# MainBoard.net
KiCad netlist of a schematic drawn in EAGLE
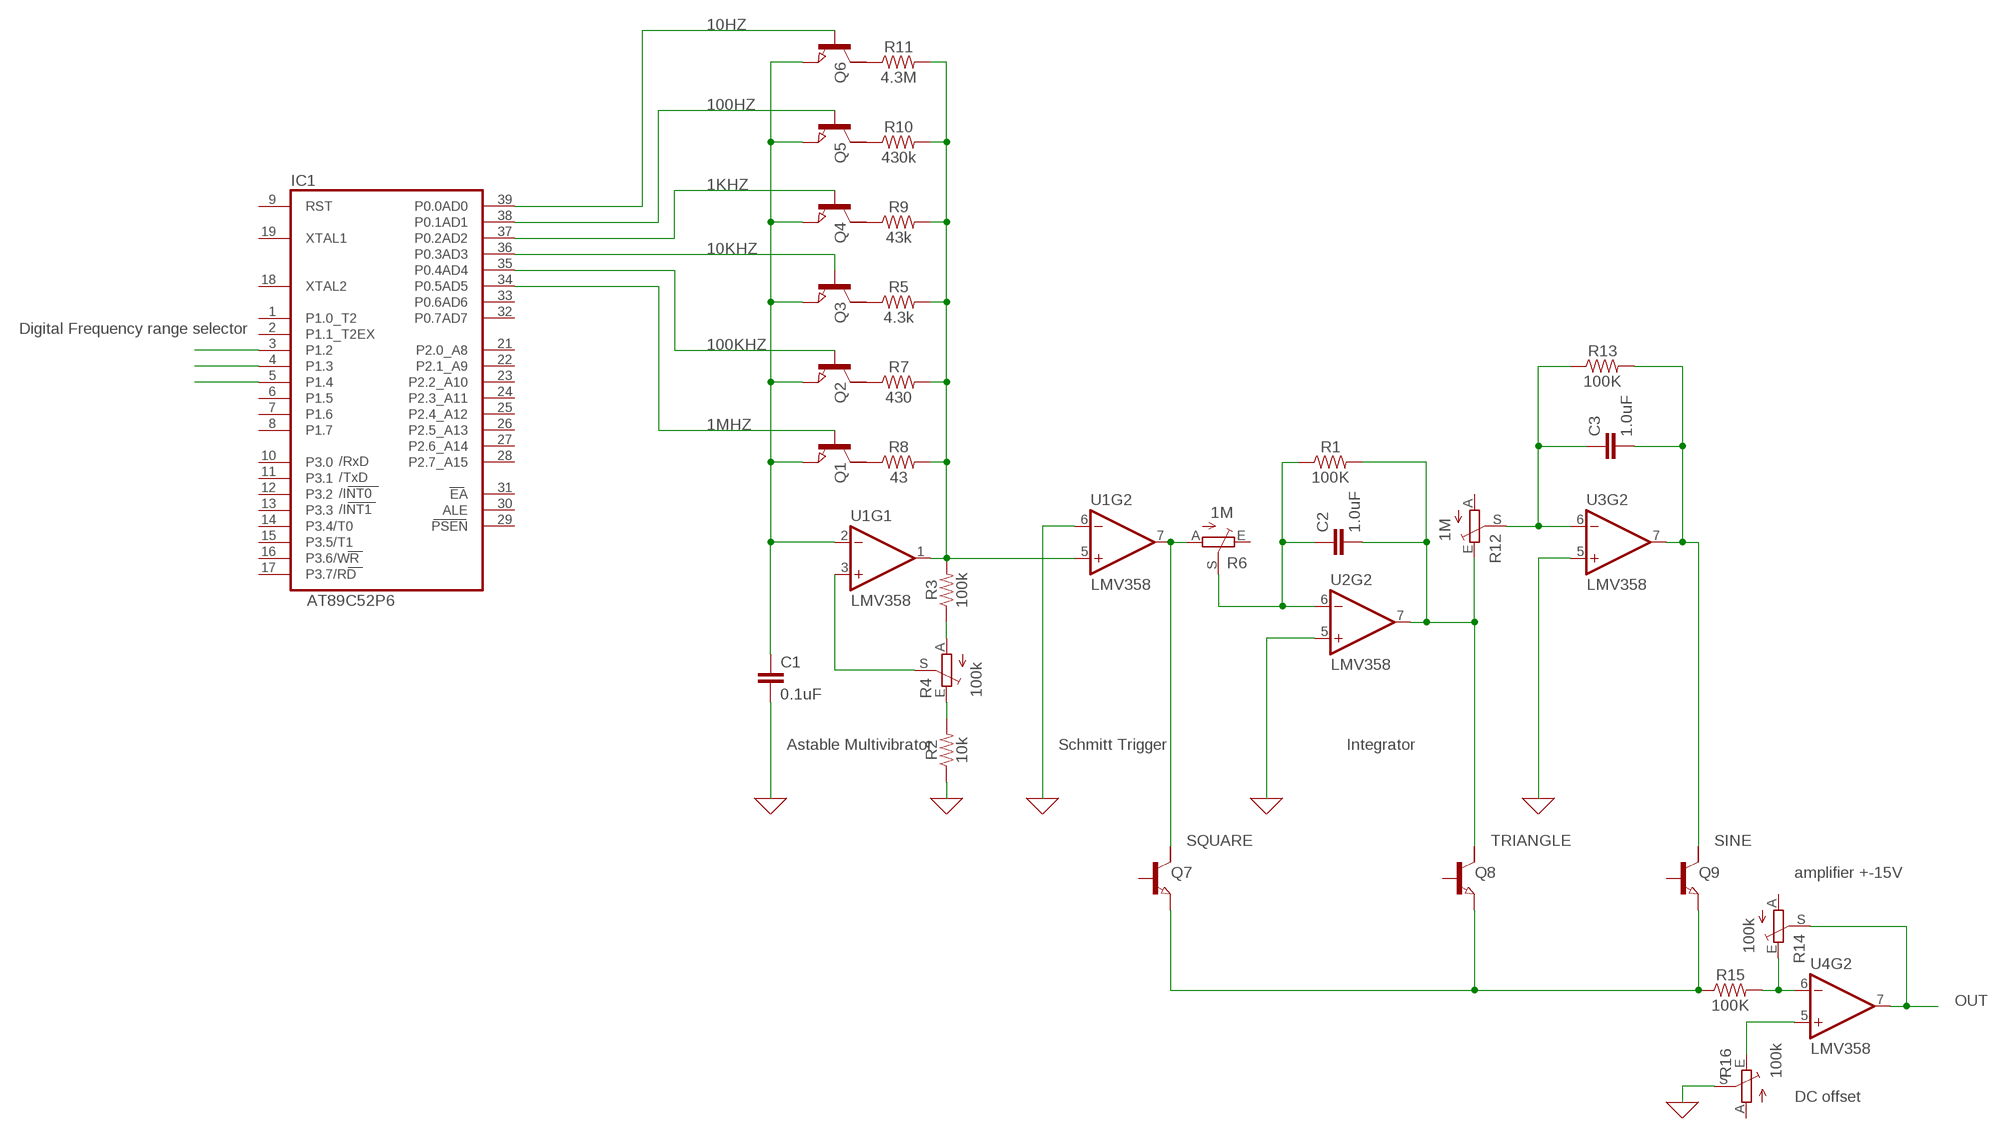
[diagram p0: schematic, sheet 1]

(export (version "E")
  (design (tool "Eeschema 10.0.6"))
  (components
    (comp (ref "C1")
      (value "0.1uF")
      (footprint "eagle-import:0402")
      (libsource (lib "eagle-import") (part "0.1UF-0402-16V-10%"))
    )
    (comp (ref "C2")
      (value "1.0uF")
      (footprint "eagle-import:0402")
      (libsource (lib "eagle-import") (part "1.0UF-0402-16V-10%"))
    )
    (comp (ref "C3")
      (value "1.0uF")
      (footprint "eagle-import:0402")
      (libsource (lib "eagle-import") (part "1.0UF-0402-16V-10%"))
    )
    (comp (ref "IC1")
      (value "AT89C52P6")
      (footprint "eagle-import:DIL40")
      (libsource (lib "eagle-import") (part "AT89C52P6"))
    )
    (comp (ref "Q1")
      (value "NPN-TRANSISTIOR-2COLSOT89")
      (footprint "eagle-import:SOT89")
      (libsource (lib "eagle-import") (part "NPN-TRANSISTIOR-2COLSOT89"))
    )
    (comp (ref "Q2")
      (value "NPN-TRANSISTIOR-2COLSOT89")
      (footprint "eagle-import:SOT89")
      (libsource (lib "eagle-import") (part "NPN-TRANSISTIOR-2COLSOT89"))
    )
    (comp (ref "Q3")
      (value "NPN-TRANSISTIOR-2COLSOT89")
      (footprint "eagle-import:SOT89")
      (libsource (lib "eagle-import") (part "NPN-TRANSISTIOR-2COLSOT89"))
    )
    (comp (ref "Q4")
      (value "NPN-TRANSISTIOR-2COLSOT89")
      (footprint "eagle-import:SOT89")
      (libsource (lib "eagle-import") (part "NPN-TRANSISTIOR-2COLSOT89"))
    )
    (comp (ref "Q5")
      (value "NPN-TRANSISTIOR-2COLSOT89")
      (footprint "eagle-import:SOT89")
      (libsource (lib "eagle-import") (part "NPN-TRANSISTIOR-2COLSOT89"))
    )
    (comp (ref "Q6")
      (value "NPN-TRANSISTIOR-2COLSOT89")
      (footprint "eagle-import:SOT89")
      (libsource (lib "eagle-import") (part "NPN-TRANSISTIOR-2COLSOT89"))
    )
    (comp (ref "Q7")
      (value "NPN-TRANSISTIOR-2COLSOT89")
      (footprint "eagle-import:SOT89")
      (libsource (lib "eagle-import") (part "NPN-TRANSISTIOR-2COLSOT89"))
    )
    (comp (ref "Q8")
      (value "NPN-TRANSISTIOR-2COLSOT89")
      (footprint "eagle-import:SOT89")
      (libsource (lib "eagle-import") (part "NPN-TRANSISTIOR-2COLSOT89"))
    )
    (comp (ref "Q9")
      (value "NPN-TRANSISTIOR-2COLSOT89")
      (footprint "eagle-import:SOT89")
      (libsource (lib "eagle-import") (part "NPN-TRANSISTIOR-2COLSOT89"))
    )
    (comp (ref "R1")
      (value "100K")
      (footprint "eagle-import:0402")
      (libsource (lib "eagle-import") (part "100KOHM-0402-1/16W-1%"))
    )
    (comp (ref "R2")
      (value "10k")
      (footprint "eagle-import:0603")
      (libsource (lib "eagle-import") (part "715OHM-0603-1/10W-1%"))
    )
    (comp (ref "R3")
      (value "100k")
      (footprint "eagle-import:0603")
      (libsource (lib "eagle-import") (part "220KOHM-0603-1/10W-1%"))
    )
    (comp (ref "R4")
      (value "100k")
      (footprint "eagle-import:S64YW")
      (libsource (lib "eagle-import") (part "TRIM_1234-S64YW"))
    )
    (comp (ref "R5")
      (value "4.3k")
      (footprint "eagle-import:0603")
      (libsource (lib "eagle-import") (part "43KOHM-0603-1/10W-1%"))
    )
    (comp (ref "R6")
      (value "1M")
      (footprint "eagle-import:S64YW")
      (libsource (lib "eagle-import") (part "TRIM_1234-S64YW"))
    )
    (comp (ref "R7")
      (value "430")
      (footprint "eagle-import:0603")
      (libsource (lib "eagle-import") (part "43KOHM-0603-1/10W-1%"))
    )
    (comp (ref "R8")
      (value "43")
      (footprint "eagle-import:0603")
      (libsource (lib "eagle-import") (part "43KOHM-0603-1/10W-1%"))
    )
    (comp (ref "R9")
      (value "43k")
      (footprint "eagle-import:0603")
      (libsource (lib "eagle-import") (part "43KOHM-0603-1/10W-1%"))
    )
    (comp (ref "R10")
      (value "430k")
      (footprint "eagle-import:0603")
      (libsource (lib "eagle-import") (part "43KOHM-0603-1/10W-1%"))
    )
    (comp (ref "R11")
      (value "4.3M")
      (footprint "eagle-import:0603")
      (libsource (lib "eagle-import") (part "43KOHM-0603-1/10W-1%"))
    )
    (comp (ref "R12")
      (value "1M")
      (footprint "eagle-import:S64YW")
      (libsource (lib "eagle-import") (part "TRIM_1234-S64YW"))
    )
    (comp (ref "R13")
      (value "100K")
      (footprint "eagle-import:0402")
      (libsource (lib "eagle-import") (part "100KOHM-0402-1/16W-1%"))
    )
    (comp (ref "R14")
      (value "100k")
      (footprint "eagle-import:S64YW")
      (libsource (lib "eagle-import") (part "TRIM_1234-S64YW"))
    )
    (comp (ref "R15")
      (value "100K")
      (footprint "eagle-import:0402")
      (libsource (lib "eagle-import") (part "100KOHM-0402-1/16W-1%"))
    )
    (comp (ref "R16")
      (value "100k")
      (footprint "eagle-import:S64YW")
      (libsource (lib "eagle-import") (part "TRIM_1234-S64YW"))
    )
    (comp (ref "U1")
      (value "LMV358")
      (footprint "eagle-import:SO08")
      (libsource (lib "eagle-import") (part "LMV358SOIC"))
    )
    (comp (ref "U2")
      (value "LMV358")
      (footprint "eagle-import:SO08")
      (libsource (lib "eagle-import") (part "LMV358SOIC"))
    )
    (comp (ref "U3")
      (value "LMV358")
      (footprint "eagle-import:SO08")
      (libsource (lib "eagle-import") (part "LMV358SOIC"))
    )
    (comp (ref "U4")
      (value "LMV358")
      (footprint "eagle-import:SO08")
      (libsource (lib "eagle-import") (part "LMV358SOIC"))
    )
  )
  (nets
    (net (code "1") (name "/1KHZ") (class "Default")
      (node (ref "IC1") (pin "37") (pinfunction "P0.2AD2_37") (pintype "bidirectional"))
      (node (ref "Q4") (pin "1") (pinfunction "B_1") (pintype "passive"))
    )
    (net (code "2") (name "/1MHZ") (class "Default")
      (node (ref "IC1") (pin "34") (pinfunction "P0.5AD5_34") (pintype "bidirectional"))
      (node (ref "Q1") (pin "1") (pinfunction "B_1") (pintype "passive"))
    )
    (net (code "3") (name "/10HZ") (class "Default")
      (node (ref "IC1") (pin "39") (pinfunction "P0.0AD0_39") (pintype "bidirectional"))
      (node (ref "Q6") (pin "1") (pinfunction "B_1") (pintype "passive"))
    )
    (net (code "4") (name "/10KHZ") (class "Default")
      (node (ref "IC1") (pin "36") (pinfunction "P0.3AD3_36") (pintype "bidirectional"))
      (node (ref "Q3") (pin "1") (pinfunction "B_1") (pintype "passive"))
    )
    (net (code "5") (name "/100HZ") (class "Default")
      (node (ref "IC1") (pin "38") (pinfunction "P0.1AD1_38") (pintype "bidirectional"))
      (node (ref "Q5") (pin "1") (pinfunction "B_1") (pintype "passive"))
    )
    (net (code "6") (name "/100KHZ") (class "Default")
      (node (ref "IC1") (pin "35") (pinfunction "P0.4AD4_35") (pintype "bidirectional"))
      (node (ref "Q2") (pin "1") (pinfunction "B_1") (pintype "passive"))
    )
    (net (code "7") (name "/OUT") (class "Default")
      (node (ref "R14") (pin "S") (pinfunction "S_S") (pintype "passive"))
      (node (ref "U4") (pin "7") (pinfunction "OUT_7") (pintype "output"))
    )
    (net (code "8") (name "/SINE") (class "Default")
      (node (ref "C3") (pin "2") (pinfunction "2_2") (pintype "passive"))
      (node (ref "Q9") (pin "2") (pinfunction "C_2") (pintype "passive"))
      (node (ref "R13") (pin "2") (pinfunction "2_2") (pintype "passive"))
      (node (ref "U3") (pin "7") (pinfunction "OUT_7") (pintype "output"))
    )
    (net (code "9") (name "/SQUARE") (class "Default")
      (node (ref "Q7") (pin "2") (pinfunction "C_2") (pintype "passive"))
      (node (ref "R6") (pin "A") (pinfunction "A_A") (pintype "passive"))
      (node (ref "U1") (pin "7") (pinfunction "OUT_7") (pintype "output"))
    )
    (net (code "10") (name "/TRIANGLE") (class "Default")
      (node (ref "C2") (pin "2") (pinfunction "2_2") (pintype "passive"))
      (node (ref "Q8") (pin "2") (pinfunction "C_2") (pintype "passive"))
      (node (ref "R1") (pin "2") (pinfunction "2_2") (pintype "passive"))
      (node (ref "R12") (pin "E") (pinfunction "E_E") (pintype "passive"))
      (node (ref "U2") (pin "7") (pinfunction "OUT_7") (pintype "output"))
    )
    (net (code "11") (name "GND") (class "Default")
      (node (ref "C1") (pin "2") (pinfunction "2_2") (pintype "passive"))
      (node (ref "R16") (pin "S") (pinfunction "S_S") (pintype "passive"))
      (node (ref "R2") (pin "1") (pinfunction "1_1") (pintype "passive"))
      (node (ref "U1") (pin "6") (pinfunction "-IN_6") (pintype "input"))
      (node (ref "U2") (pin "5") (pinfunction "+IN_5") (pintype "input"))
      (node (ref "U3") (pin "5") (pinfunction "+IN_5") (pintype "input"))
    )
    (net (code "12") (name "Net-(Q1-C)") (class "Default")
      (node (ref "Q1") (pin "2") (pinfunction "C_2") (pintype "passive"))
      (node (ref "R8") (pin "1") (pinfunction "1_1") (pintype "passive"))
    )
    (net (code "13") (name "Net-(Q1-E)") (class "Default")
      (node (ref "C1") (pin "1") (pinfunction "1_1") (pintype "passive"))
      (node (ref "Q1") (pin "3") (pinfunction "E_3") (pintype "passive"))
      (node (ref "Q2") (pin "3") (pinfunction "E_3") (pintype "passive"))
      (node (ref "Q3") (pin "3") (pinfunction "E_3") (pintype "passive"))
      (node (ref "Q4") (pin "3") (pinfunction "E_3") (pintype "passive"))
      (node (ref "Q5") (pin "3") (pinfunction "E_3") (pintype "passive"))
      (node (ref "Q6") (pin "3") (pinfunction "E_3") (pintype "passive"))
      (node (ref "U1") (pin "2") (pinfunction "-IN_2") (pintype "input"))
    )
    (net (code "14") (name "Net-(Q2-C)") (class "Default")
      (node (ref "Q2") (pin "2") (pinfunction "C_2") (pintype "passive"))
      (node (ref "R7") (pin "1") (pinfunction "1_1") (pintype "passive"))
    )
    (net (code "15") (name "Net-(Q3-C)") (class "Default")
      (node (ref "Q3") (pin "2") (pinfunction "C_2") (pintype "passive"))
      (node (ref "R5") (pin "1") (pinfunction "1_1") (pintype "passive"))
    )
    (net (code "16") (name "Net-(Q4-C)") (class "Default")
      (node (ref "Q4") (pin "2") (pinfunction "C_2") (pintype "passive"))
      (node (ref "R9") (pin "1") (pinfunction "1_1") (pintype "passive"))
    )
    (net (code "17") (name "Net-(Q5-C)") (class "Default")
      (node (ref "Q5") (pin "2") (pinfunction "C_2") (pintype "passive"))
      (node (ref "R10") (pin "1") (pinfunction "1_1") (pintype "passive"))
    )
    (net (code "18") (name "Net-(Q6-C)") (class "Default")
      (node (ref "Q6") (pin "2") (pinfunction "C_2") (pintype "passive"))
      (node (ref "R11") (pin "1") (pinfunction "1_1") (pintype "passive"))
    )
    (net (code "19") (name "Net-(Q7-E)") (class "Default")
      (node (ref "Q7") (pin "3") (pinfunction "E_3") (pintype "passive"))
      (node (ref "Q8") (pin "3") (pinfunction "E_3") (pintype "passive"))
      (node (ref "Q9") (pin "3") (pinfunction "E_3") (pintype "passive"))
      (node (ref "R15") (pin "1") (pinfunction "1_1") (pintype "passive"))
    )
    (net (code "20") (name "Net-(R2-Pad2)") (class "Default")
      (node (ref "R2") (pin "2") (pinfunction "2_2") (pintype "passive"))
      (node (ref "R4") (pin "E") (pinfunction "E_E") (pintype "passive"))
    )
    (net (code "21") (name "Net-(R3-Pad1)") (class "Default")
      (node (ref "R3") (pin "1") (pinfunction "1_1") (pintype "passive"))
      (node (ref "R4") (pin "A") (pinfunction "A_A") (pintype "passive"))
    )
    (net (code "22") (name "Net-(U1A-+IN)") (class "Default")
      (node (ref "R4") (pin "S") (pinfunction "S_S") (pintype "passive"))
      (node (ref "U1") (pin "3") (pinfunction "+IN_3") (pintype "input"))
    )
    (net (code "23") (name "Net-(U1A-OUT)") (class "Default")
      (node (ref "R10") (pin "2") (pinfunction "2_2") (pintype "passive"))
      (node (ref "R11") (pin "2") (pinfunction "2_2") (pintype "passive"))
      (node (ref "R3") (pin "2") (pinfunction "2_2") (pintype "passive"))
      (node (ref "R5") (pin "2") (pinfunction "2_2") (pintype "passive"))
      (node (ref "R7") (pin "2") (pinfunction "2_2") (pintype "passive"))
      (node (ref "R8") (pin "2") (pinfunction "2_2") (pintype "passive"))
      (node (ref "R9") (pin "2") (pinfunction "2_2") (pintype "passive"))
      (node (ref "U1") (pin "1") (pinfunction "OUT_1") (pintype "output"))
      (node (ref "U1") (pin "5") (pinfunction "+IN_5") (pintype "input"))
    )
    (net (code "24") (name "Net-(U2B--IN)") (class "Default")
      (node (ref "C2") (pin "1") (pinfunction "1_1") (pintype "passive"))
      (node (ref "R1") (pin "1") (pinfunction "1_1") (pintype "passive"))
      (node (ref "R6") (pin "S") (pinfunction "S_S") (pintype "passive"))
      (node (ref "U2") (pin "6") (pinfunction "-IN_6") (pintype "input"))
    )
    (net (code "25") (name "Net-(U3B--IN)") (class "Default")
      (node (ref "C3") (pin "1") (pinfunction "1_1") (pintype "passive"))
      (node (ref "R12") (pin "S") (pinfunction "S_S") (pintype "passive"))
      (node (ref "R13") (pin "1") (pinfunction "1_1") (pintype "passive"))
      (node (ref "U3") (pin "6") (pinfunction "-IN_6") (pintype "input"))
    )
    (net (code "26") (name "Net-(U4B-+IN)") (class "Default")
      (node (ref "R16") (pin "E") (pinfunction "E_E") (pintype "passive"))
      (node (ref "U4") (pin "5") (pinfunction "+IN_5") (pintype "input"))
    )
    (net (code "27") (name "Net-(U4B--IN)") (class "Default")
      (node (ref "R14") (pin "E") (pinfunction "E_E") (pintype "passive"))
      (node (ref "R15") (pin "2") (pinfunction "2_2") (pintype "passive"))
      (node (ref "U4") (pin "6") (pinfunction "-IN_6") (pintype "input"))
    )
    (net (code "28") (name "unconnected-(IC1A-ALE-Pad30)") (class "Default")
      (node (ref "IC1") (pin "30") (pinfunction "ALE_30") (pintype "output"))
    )
    (net (code "29") (name "unconnected-(IC1A-EA-Pad31)") (class "Default")
      (node (ref "IC1") (pin "31") (pinfunction "EA_31") (pintype "input"))
    )
    (net (code "30") (name "unconnected-(IC1A-P0.6AD6-Pad33)") (class "Default")
      (node (ref "IC1") (pin "33") (pinfunction "P0.6AD6_33") (pintype "bidirectional"))
    )
    (net (code "31") (name "unconnected-(IC1A-P0.7AD7-Pad32)") (class "Default")
      (node (ref "IC1") (pin "32") (pinfunction "P0.7AD7_32") (pintype "bidirectional"))
    )
    (net (code "32") (name "unconnected-(IC1A-P1.0_T2-Pad1)") (class "Default")
      (node (ref "IC1") (pin "1") (pinfunction "P1.0_T2_1") (pintype "bidirectional"))
    )
    (net (code "33") (name "unconnected-(IC1A-P1.1_T2EX-Pad2)") (class "Default")
      (node (ref "IC1") (pin "2") (pinfunction "P1.1_T2EX_2") (pintype "bidirectional"))
    )
    (net (code "34") (name "unconnected-(IC1A-P1.2-Pad3)") (class "Default")
      (node (ref "IC1") (pin "3") (pinfunction "P1.2_3") (pintype "bidirectional"))
    )
    (net (code "35") (name "unconnected-(IC1A-P1.3-Pad4)") (class "Default")
      (node (ref "IC1") (pin "4") (pinfunction "P1.3_4") (pintype "bidirectional"))
    )
    (net (code "36") (name "unconnected-(IC1A-P1.4-Pad5)") (class "Default")
      (node (ref "IC1") (pin "5") (pinfunction "P1.4_5") (pintype "bidirectional"))
    )
    (net (code "37") (name "unconnected-(IC1A-P1.5-Pad6)") (class "Default")
      (node (ref "IC1") (pin "6") (pinfunction "P1.5_6") (pintype "bidirectional"))
    )
    (net (code "38") (name "unconnected-(IC1A-P1.6-Pad7)") (class "Default")
      (node (ref "IC1") (pin "7") (pinfunction "P1.6_7") (pintype "bidirectional"))
    )
    (net (code "39") (name "unconnected-(IC1A-P1.7-Pad8)") (class "Default")
      (node (ref "IC1") (pin "8") (pinfunction "P1.7_8") (pintype "bidirectional"))
    )
    (net (code "40") (name "unconnected-(IC1A-P2.0_A8-Pad21)") (class "Default")
      (node (ref "IC1") (pin "21") (pinfunction "P2.0_A8_21") (pintype "bidirectional"))
    )
    (net (code "41") (name "unconnected-(IC1A-P2.1_A9-Pad22)") (class "Default")
      (node (ref "IC1") (pin "22") (pinfunction "P2.1_A9_22") (pintype "bidirectional"))
    )
    (net (code "42") (name "unconnected-(IC1A-P2.2_A10-Pad23)") (class "Default")
      (node (ref "IC1") (pin "23") (pinfunction "P2.2_A10_23") (pintype "bidirectional"))
    )
    (net (code "43") (name "unconnected-(IC1A-P2.3_A11-Pad24)") (class "Default")
      (node (ref "IC1") (pin "24") (pinfunction "P2.3_A11_24") (pintype "bidirectional"))
    )
    (net (code "44") (name "unconnected-(IC1A-P2.4_A12-Pad25)") (class "Default")
      (node (ref "IC1") (pin "25") (pinfunction "P2.4_A12_25") (pintype "bidirectional"))
    )
    (net (code "45") (name "unconnected-(IC1A-P2.5_A13-Pad26)") (class "Default")
      (node (ref "IC1") (pin "26") (pinfunction "P2.5_A13_26") (pintype "bidirectional"))
    )
    (net (code "46") (name "unconnected-(IC1A-P2.6_A14-Pad27)") (class "Default")
      (node (ref "IC1") (pin "27") (pinfunction "P2.6_A14_27") (pintype "bidirectional"))
    )
    (net (code "47") (name "unconnected-(IC1A-P2.7_A15-Pad28)") (class "Default")
      (node (ref "IC1") (pin "28") (pinfunction "P2.7_A15_28") (pintype "bidirectional"))
    )
    (net (code "48") (name "unconnected-(IC1A-P3.0-Pad10)") (class "Default")
      (node (ref "IC1") (pin "10") (pinfunction "P3.0_10") (pintype "bidirectional"))
    )
    (net (code "49") (name "unconnected-(IC1A-P3.1-Pad11)") (class "Default")
      (node (ref "IC1") (pin "11") (pinfunction "P3.1_11") (pintype "bidirectional"))
    )
    (net (code "50") (name "unconnected-(IC1A-P3.2-Pad12)") (class "Default")
      (node (ref "IC1") (pin "12") (pinfunction "P3.2_12") (pintype "bidirectional"))
    )
    (net (code "51") (name "unconnected-(IC1A-P3.3-Pad13)") (class "Default")
      (node (ref "IC1") (pin "13") (pinfunction "P3.3_13") (pintype "bidirectional"))
    )
    (net (code "52") (name "unconnected-(IC1A-P3.4{slash}T0-Pad14)") (class "Default")
      (node (ref "IC1") (pin "14") (pinfunction "P3.4/T0_14") (pintype "bidirectional"))
    )
    (net (code "53") (name "unconnected-(IC1A-P3.5{slash}T1-Pad15)") (class "Default")
      (node (ref "IC1") (pin "15") (pinfunction "P3.5/T1_15") (pintype "bidirectional"))
    )
    (net (code "54") (name "unconnected-(IC1A-P3.6{slash}WR-Pad16)") (class "Default")
      (node (ref "IC1") (pin "16") (pinfunction "P3.6/WR_16") (pintype "bidirectional"))
    )
    (net (code "55") (name "unconnected-(IC1A-P3.7{slash}RD-Pad17)") (class "Default")
      (node (ref "IC1") (pin "17") (pinfunction "P3.7/RD_17") (pintype "bidirectional"))
    )
    (net (code "56") (name "unconnected-(IC1A-PSEN-Pad29)") (class "Default")
      (node (ref "IC1") (pin "29") (pinfunction "PSEN_29") (pintype "output"))
    )
    (net (code "57") (name "unconnected-(IC1A-RST-Pad9)") (class "Default")
      (node (ref "IC1") (pin "9") (pinfunction "RST_9") (pintype "input"))
    )
    (net (code "58") (name "unconnected-(IC1A-XTAL1-Pad19)") (class "Default")
      (node (ref "IC1") (pin "19") (pinfunction "XTAL1_19") (pintype "input"))
    )
    (net (code "59") (name "unconnected-(IC1A-XTAL2-Pad18)") (class "Default")
      (node (ref "IC1") (pin "18") (pinfunction "XTAL2_18") (pintype "input"))
    )
    (net (code "60") (name "unconnected-(Q1-C{slash}-Pad2@1)") (class "Default")
      (node (ref "Q1") (pin "2@1") (pinfunction "C/_2@1") (pintype "passive"))
    )
    (net (code "61") (name "unconnected-(Q2-C{slash}-Pad2@1)") (class "Default")
      (node (ref "Q2") (pin "2@1") (pinfunction "C/_2@1") (pintype "passive"))
    )
    (net (code "62") (name "unconnected-(Q3-C{slash}-Pad2@1)") (class "Default")
      (node (ref "Q3") (pin "2@1") (pinfunction "C/_2@1") (pintype "passive"))
    )
    (net (code "63") (name "unconnected-(Q4-C{slash}-Pad2@1)") (class "Default")
      (node (ref "Q4") (pin "2@1") (pinfunction "C/_2@1") (pintype "passive"))
    )
    (net (code "64") (name "unconnected-(Q5-C{slash}-Pad2@1)") (class "Default")
      (node (ref "Q5") (pin "2@1") (pinfunction "C/_2@1") (pintype "passive"))
    )
    (net (code "65") (name "unconnected-(Q6-C{slash}-Pad2@1)") (class "Default")
      (node (ref "Q6") (pin "2@1") (pinfunction "C/_2@1") (pintype "passive"))
    )
    (net (code "66") (name "unconnected-(Q7-B-Pad1)") (class "Default")
      (node (ref "Q7") (pin "1") (pinfunction "B_1") (pintype "passive"))
    )
    (net (code "67") (name "unconnected-(Q7-C{slash}-Pad2@1)") (class "Default")
      (node (ref "Q7") (pin "2@1") (pinfunction "C/_2@1") (pintype "passive"))
    )
    (net (code "68") (name "unconnected-(Q8-B-Pad1)") (class "Default")
      (node (ref "Q8") (pin "1") (pinfunction "B_1") (pintype "passive"))
    )
    (net (code "69") (name "unconnected-(Q8-C{slash}-Pad2@1)") (class "Default")
      (node (ref "Q8") (pin "2@1") (pinfunction "C/_2@1") (pintype "passive"))
    )
    (net (code "70") (name "unconnected-(Q9-B-Pad1)") (class "Default")
      (node (ref "Q9") (pin "1") (pinfunction "B_1") (pintype "passive"))
    )
    (net (code "71") (name "unconnected-(Q9-C{slash}-Pad2@1)") (class "Default")
      (node (ref "Q9") (pin "2@1") (pinfunction "C/_2@1") (pintype "passive"))
    )
    (net (code "72") (name "unconnected-(R4-S-PadS@1)") (class "Default")
      (node (ref "R4") (pin "S@1") (pinfunction "S_S@1") (pintype "passive"))
    )
    (net (code "73") (name "unconnected-(R6-PadE)") (class "Default")
      (node (ref "R6") (pin "E") (pinfunction "E_E") (pintype "passive"))
    )
    (net (code "74") (name "unconnected-(R6-S-PadS@1)") (class "Default")
      (node (ref "R6") (pin "S@1") (pinfunction "S_S@1") (pintype "passive"))
    )
    (net (code "75") (name "unconnected-(R12-PadA)") (class "Default")
      (node (ref "R12") (pin "A") (pinfunction "A_A") (pintype "passive"))
    )
    (net (code "76") (name "unconnected-(R12-S-PadS@1)") (class "Default")
      (node (ref "R12") (pin "S@1") (pinfunction "S_S@1") (pintype "passive"))
    )
    (net (code "77") (name "unconnected-(R14-PadA)") (class "Default")
      (node (ref "R14") (pin "A") (pinfunction "A_A") (pintype "passive"))
    )
    (net (code "78") (name "unconnected-(R14-S-PadS@1)") (class "Default")
      (node (ref "R14") (pin "S@1") (pinfunction "S_S@1") (pintype "passive"))
    )
    (net (code "79") (name "unconnected-(R16-PadA)") (class "Default")
      (node (ref "R16") (pin "A") (pinfunction "A_A") (pintype "passive"))
    )
    (net (code "80") (name "unconnected-(R16-S-PadS@1)") (class "Default")
      (node (ref "R16") (pin "S@1") (pinfunction "S_S@1") (pintype "passive"))
    )
  )
)
